# RPI_SmartServo_th_v3.net
KiCad netlist of a schematic drawn in EAGLE
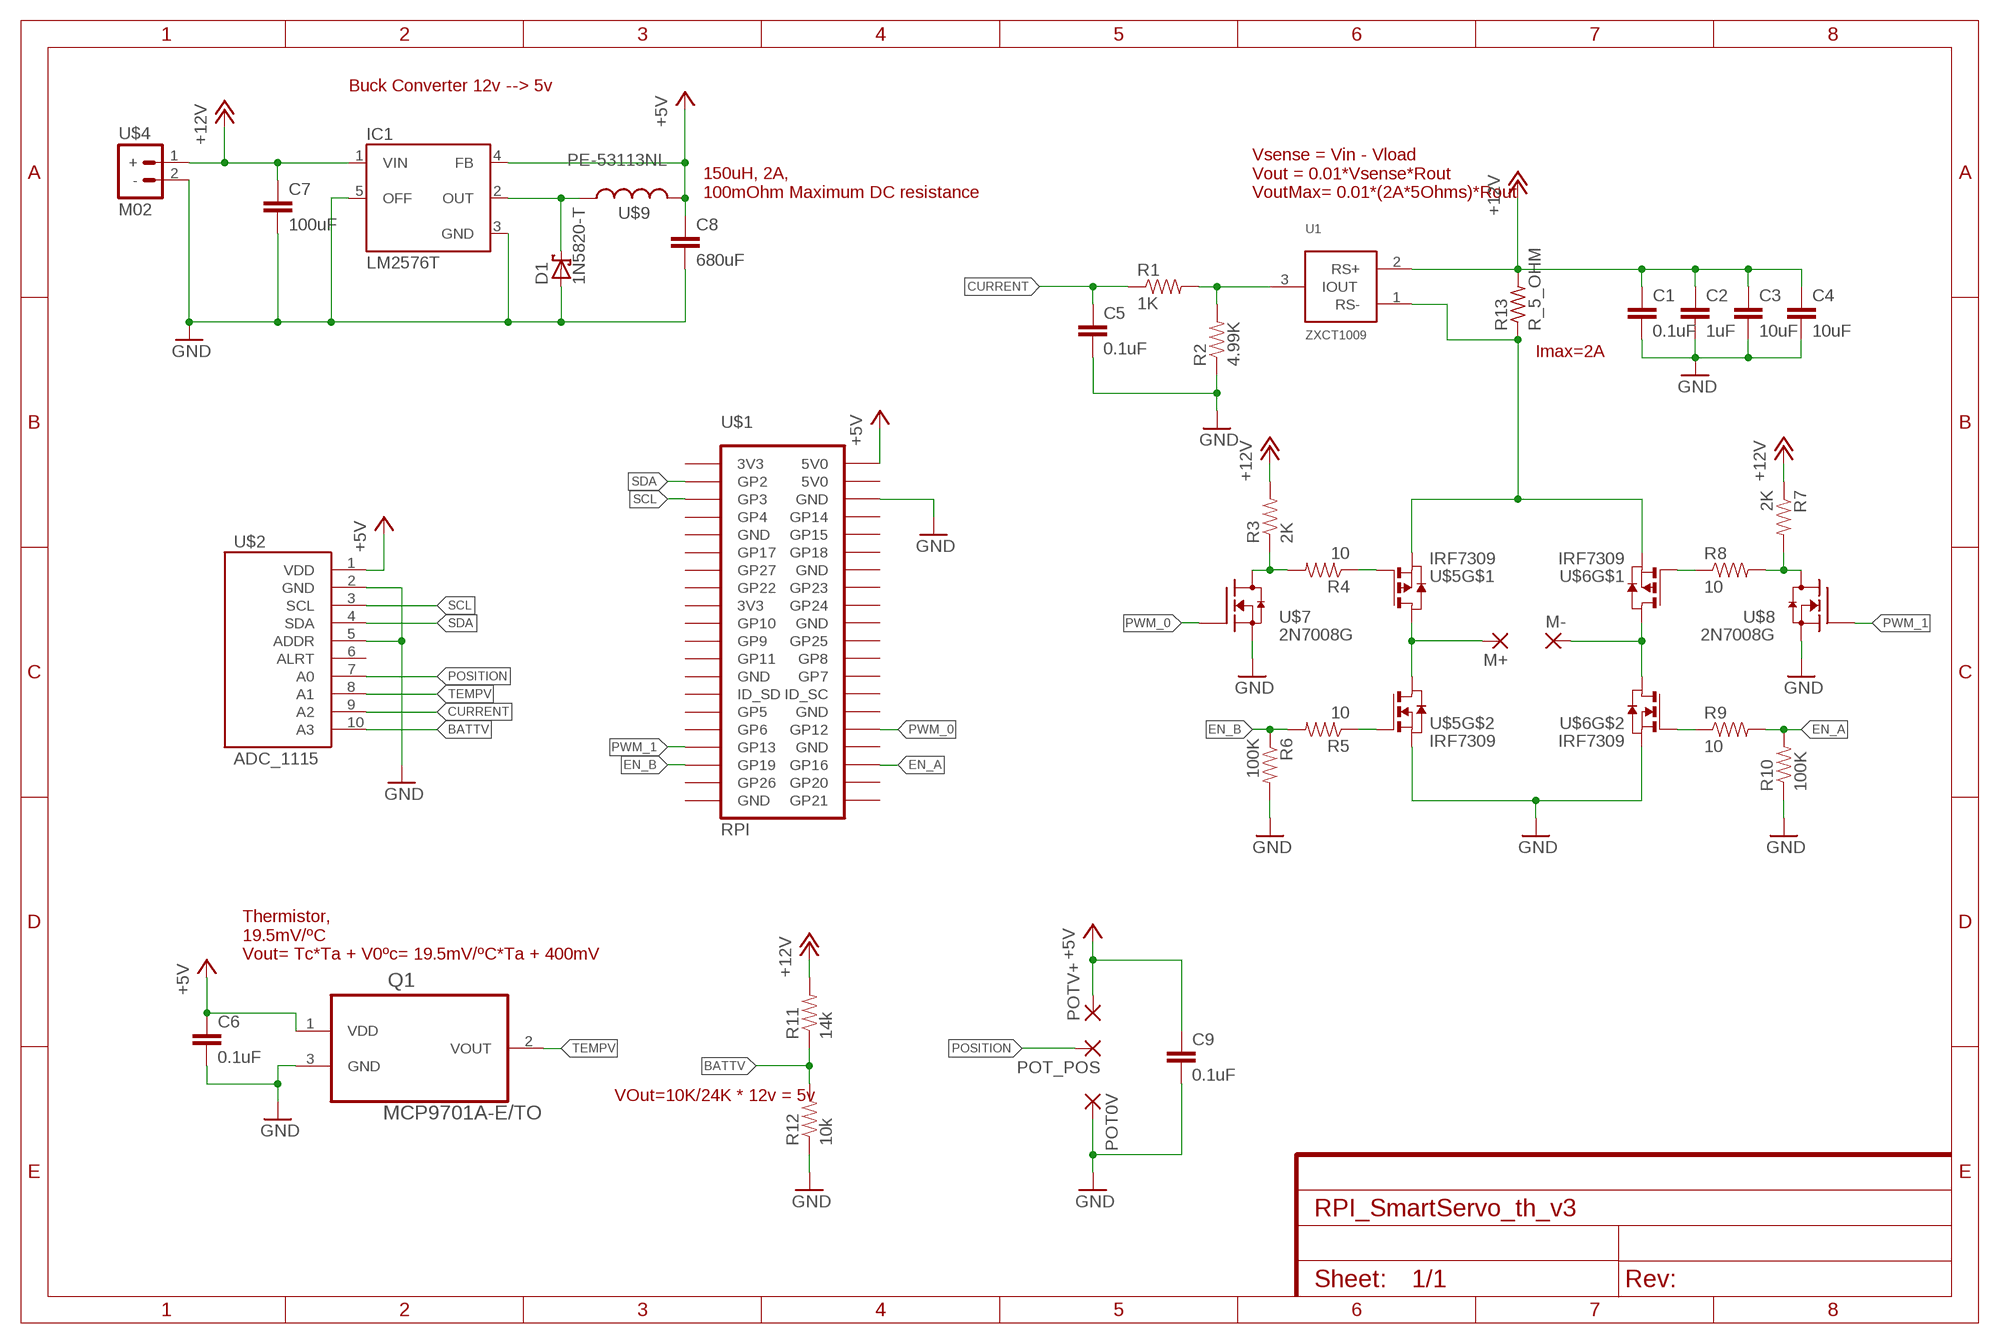
[diagram p0: schematic, sheet 1]

(export (version "E")
  (design (tool "Eeschema 10.0.6"))
  (components
    (comp (ref "C1")
      (value "0.1uF")
      (footprint "eagle-import:C025-025X050")
      (libsource (lib "eagle-import") (part "C-EU025-025X050"))
    )
    (comp (ref "C2")
      (value "1uF")
      (footprint "eagle-import:C025-025X050")
      (libsource (lib "eagle-import") (part "C-EU025-025X050"))
    )
    (comp (ref "C3")
      (value "10uF")
      (footprint "eagle-import:C025-025X050")
      (libsource (lib "eagle-import") (part "C-EU025-025X050"))
    )
    (comp (ref "C4")
      (value "10uF")
      (footprint "eagle-import:C025-025X050")
      (libsource (lib "eagle-import") (part "C-EU025-025X050"))
    )
    (comp (ref "C5")
      (value "0.1uF")
      (footprint "eagle-import:C025-025X050")
      (libsource (lib "eagle-import") (part "C-EU025-025X050"))
    )
    (comp (ref "C6")
      (value "0.1uF")
      (footprint "eagle-import:C025-025X050")
      (libsource (lib "eagle-import") (part "C-EU025-025X050"))
    )
    (comp (ref "C7")
      (value "100uF")
      (footprint "eagle-import:C025-025X050")
      (libsource (lib "eagle-import") (part "C-EU025-025X050"))
    )
    (comp (ref "C8")
      (value "680uF")
      (footprint "eagle-import:C025-025X050")
      (libsource (lib "eagle-import") (part "C-EU025-025X050"))
    )
    (comp (ref "C9")
      (value "0.1uF")
      (footprint "eagle-import:C025-025X050")
      (libsource (lib "eagle-import") (part "C-EU025-025X050"))
    )
    (comp (ref "D1")
      (value "1N5820-T")
      (footprint "eagle-import:C4111-15")
      (libsource (lib "eagle-import") (part "SCHOTTKY-DIODEC4111-15"))
    )
    (comp (ref "IC1")
      (value "LM2576T")
      (footprint "eagle-import:TO220-5")
      (libsource (lib "eagle-import") (part "LM2576T"))
    )
    (comp (ref "M+")
      (value "1,6/0,9")
      (footprint "eagle-import:1,6_0,9")
      (libsource (lib "eagle-import") (part "1,6/0,9"))
    )
    (comp (ref "M-")
      (value "1,6/0,9")
      (footprint "eagle-import:1,6_0,9")
      (libsource (lib "eagle-import") (part "1,6/0,9"))
    )
    (comp (ref "POT0V")
      (value "1,6/0,9")
      (footprint "eagle-import:1,6_0,9")
      (libsource (lib "eagle-import") (part "1,6/0,9"))
    )
    (comp (ref "POTV+")
      (value "1,6/0,9")
      (footprint "eagle-import:1,6_0,9")
      (libsource (lib "eagle-import") (part "1,6/0,9"))
    )
    (comp (ref "POT_POS")
      (value "1,6/0,9")
      (footprint "eagle-import:1,6_0,9")
      (libsource (lib "eagle-import") (part "1,6/0,9"))
    )
    (comp (ref "Q1")
      (value "MCP9701A-E/TO")
      (footprint "eagle-import:TO127P254X533-3")
      (libsource (lib "eagle-import") (part "MCP9701A-E/TO"))
    )
    (comp (ref "R1")
      (value "1K")
      (footprint "eagle-import:AXIAL-0.4")
      (libsource (lib "eagle-import") (part "RESISTORPTH-1/4W"))
    )
    (comp (ref "R2")
      (value "4.99K")
      (footprint "eagle-import:AXIAL-0.4")
      (libsource (lib "eagle-import") (part "RESISTORPTH-1/4W"))
    )
    (comp (ref "R3")
      (value "2K")
      (footprint "eagle-import:AXIAL-0.4")
      (libsource (lib "eagle-import") (part "RESISTORPTH-1/4W"))
    )
    (comp (ref "R4")
      (value "10")
      (footprint "eagle-import:AXIAL-0.4")
      (libsource (lib "eagle-import") (part "RESISTORPTH-1/4W"))
    )
    (comp (ref "R5")
      (value "10")
      (footprint "eagle-import:AXIAL-0.4")
      (libsource (lib "eagle-import") (part "RESISTORPTH-1/4W"))
    )
    (comp (ref "R6")
      (value "100K")
      (footprint "eagle-import:AXIAL-0.4")
      (libsource (lib "eagle-import") (part "RESISTORPTH-1/4W"))
    )
    (comp (ref "R7")
      (value "2K")
      (footprint "eagle-import:AXIAL-0.4")
      (libsource (lib "eagle-import") (part "RESISTORPTH-1/4W"))
    )
    (comp (ref "R8")
      (value "10")
      (footprint "eagle-import:AXIAL-0.4")
      (libsource (lib "eagle-import") (part "RESISTORPTH-1/4W"))
    )
    (comp (ref "R9")
      (value "10")
      (footprint "eagle-import:AXIAL-0.4")
      (libsource (lib "eagle-import") (part "RESISTORPTH-1/4W"))
    )
    (comp (ref "R10")
      (value "100K")
      (footprint "eagle-import:AXIAL-0.4")
      (libsource (lib "eagle-import") (part "RESISTORPTH-1/4W"))
    )
    (comp (ref "R11")
      (value "14k")
      (footprint "eagle-import:AXIAL-0.4")
      (libsource (lib "eagle-import") (part "RESISTORPTH-1/4W"))
    )
    (comp (ref "R12")
      (value "10k")
      (footprint "eagle-import:AXIAL-0.4")
      (libsource (lib "eagle-import") (part "RESISTORPTH-1/4W"))
    )
    (comp (ref "R13")
      (value "R_5_OHM")
      (footprint "eagle-import:0922_22")
      (libsource (lib "eagle-import") (part "R_5_OHM"))
    )
    (comp (ref "U$1")
      (value "RPI")
      (footprint "eagle-import:2X20")
      (libsource (lib "eagle-import") (part "RPI"))
    )
    (comp (ref "U$2")
      (value "ADC_1115")
      (footprint "eagle-import:1X10")
      (libsource (lib "eagle-import") (part "ADC_1115"))
    )
    (comp (ref "U$4")
      (value "M02")
      (footprint "eagle-import:1X02")
      (libsource (lib "eagle-import") (part "M02"))
    )
    (comp (ref "U$5")
      (value "IRF7309")
      (footprint "eagle-import:SO8")
      (libsource (lib "eagle-import") (part "IRF7309"))
    )
    (comp (ref "U$6")
      (value "IRF7309")
      (footprint "eagle-import:SO8")
      (libsource (lib "eagle-import") (part "IRF7309"))
    )
    (comp (ref "U$7")
      (value "2N7008G")
      (footprint "eagle-import:TO-92")
      (libsource (lib "eagle-import") (part "2N7008G"))
    )
    (comp (ref "U$8")
      (value "2N7008G")
      (footprint "eagle-import:TO-92")
      (libsource (lib "eagle-import") (part "2N7008G"))
    )
    (comp (ref "U$9")
      (value "PE-53113NL")
      (footprint "eagle-import:KM-4")
      (libsource (lib "eagle-import") (part "PE-53113NL"))
    )
    (comp (ref "U1")
      (value "ZXCT1009")
      (footprint "eagle-import:SOT23")
      (libsource (lib "eagle-import") (part "ZXCT1009"))
    )
  )
  (nets
    (net (code "1") (name "+5V") (class "Default")
      (node (ref "C6") (pin "1") (pinfunction "1_1") (pintype "passive"))
      (node (ref "C8") (pin "1") (pinfunction "1_1") (pintype "passive"))
      (node (ref "C9") (pin "1") (pinfunction "1_1") (pintype "passive"))
      (node (ref "IC1") (pin "4") (pinfunction "FB_4") (pintype "input"))
      (node (ref "POTV+") (pin "1") (pinfunction "P_1") (pintype "passive"))
      (node (ref "Q1") (pin "1") (pinfunction "VDD_1") (pintype "power_in"))
      (node (ref "U$1") (pin "2") (pinfunction "5V0_2") (pintype "bidirectional"))
      (node (ref "U$2") (pin "1") (pinfunction "VDD_1") (pintype "bidirectional"))
      (node (ref "U$9") (pin "P$2") (pinfunction "2_P$2") (pintype "passive"))
    )
    (net (code "2") (name "+12V") (class "Default")
      (node (ref "C1") (pin "1") (pinfunction "1_1") (pintype "passive"))
      (node (ref "C2") (pin "1") (pinfunction "1_1") (pintype "passive"))
      (node (ref "C3") (pin "1") (pinfunction "1_1") (pintype "passive"))
      (node (ref "C4") (pin "1") (pinfunction "1_1") (pintype "passive"))
      (node (ref "C7") (pin "1") (pinfunction "1_1") (pintype "passive"))
      (node (ref "IC1") (pin "1") (pinfunction "VIN_1") (pintype "power_in"))
      (node (ref "R11") (pin "P$2") (pinfunction "2_P$2") (pintype "passive"))
      (node (ref "R13") (pin "2") (pinfunction "2_2") (pintype "passive"))
      (node (ref "R3") (pin "P$2") (pinfunction "2_P$2") (pintype "passive"))
      (node (ref "R7") (pin "P$1") (pinfunction "1_P$1") (pintype "passive"))
      (node (ref "U$4") (pin "1") (pinfunction "+_1") (pintype "passive"))
      (node (ref "U1") (pin "2") (pinfunction "RS+_2") (pintype "bidirectional"))
    )
    (net (code "3") (name "BATTV") (class "Default")
      (node (ref "R11") (pin "P$1") (pinfunction "1_P$1") (pintype "passive"))
      (node (ref "R12") (pin "P$2") (pinfunction "2_P$2") (pintype "passive"))
      (node (ref "U$2") (pin "10") (pinfunction "A3_10") (pintype "bidirectional"))
    )
    (net (code "4") (name "CURRENT") (class "Default")
      (node (ref "C5") (pin "1") (pinfunction "1_1") (pintype "passive"))
      (node (ref "R1") (pin "P$1") (pinfunction "1_P$1") (pintype "passive"))
      (node (ref "U$2") (pin "9") (pinfunction "A2_9") (pintype "bidirectional"))
    )
    (net (code "5") (name "EN_A") (class "Default")
      (node (ref "R10") (pin "P$2") (pinfunction "2_P$2") (pintype "passive"))
      (node (ref "R9") (pin "P$2") (pinfunction "2_P$2") (pintype "passive"))
      (node (ref "U$1") (pin "36") (pinfunction "GP16_36") (pintype "bidirectional"))
    )
    (net (code "6") (name "EN_B") (class "Default")
      (node (ref "R5") (pin "P$2") (pinfunction "2_P$2") (pintype "passive"))
      (node (ref "R6") (pin "P$1") (pinfunction "1_P$1") (pintype "passive"))
      (node (ref "U$1") (pin "35") (pinfunction "GP19_35") (pintype "bidirectional"))
    )
    (net (code "7") (name "GND") (class "Default")
      (node (ref "C1") (pin "2") (pinfunction "2_2") (pintype "passive"))
      (node (ref "C2") (pin "2") (pinfunction "2_2") (pintype "passive"))
      (node (ref "C3") (pin "2") (pinfunction "2_2") (pintype "passive"))
      (node (ref "C4") (pin "2") (pinfunction "2_2") (pintype "passive"))
      (node (ref "C5") (pin "2") (pinfunction "2_2") (pintype "passive"))
      (node (ref "C6") (pin "2") (pinfunction "2_2") (pintype "passive"))
      (node (ref "C7") (pin "2") (pinfunction "2_2") (pintype "passive"))
      (node (ref "C8") (pin "2") (pinfunction "2_2") (pintype "passive"))
      (node (ref "C9") (pin "2") (pinfunction "2_2") (pintype "passive"))
      (node (ref "D1") (pin "A") (pinfunction "A_A") (pintype "passive"))
      (node (ref "IC1") (pin "3") (pinfunction "GND_3") (pintype "power_in"))
      (node (ref "IC1") (pin "5") (pinfunction "OFF_5") (pintype "input"))
      (node (ref "POT0V") (pin "1") (pinfunction "P_1") (pintype "passive"))
      (node (ref "Q1") (pin "3") (pinfunction "GND_3") (pintype "passive"))
      (node (ref "R10") (pin "P$1") (pinfunction "1_P$1") (pintype "passive"))
      (node (ref "R12") (pin "P$1") (pinfunction "1_P$1") (pintype "passive"))
      (node (ref "R2") (pin "P$1") (pinfunction "1_P$1") (pintype "passive"))
      (node (ref "R6") (pin "P$2") (pinfunction "2_P$2") (pintype "passive"))
      (node (ref "U$1") (pin "6") (pinfunction "GND_6") (pintype "bidirectional"))
      (node (ref "U$2") (pin "2") (pinfunction "GND_2") (pintype "bidirectional"))
      (node (ref "U$2") (pin "5") (pinfunction "ADDR_5") (pintype "bidirectional"))
      (node (ref "U$4") (pin "2") (pinfunction "-_2") (pintype "passive"))
      (node (ref "U$5") (pin "1") (pinfunction "S_1") (pintype "passive"))
      (node (ref "U$6") (pin "1") (pinfunction "S_1") (pintype "passive"))
      (node (ref "U$7") (pin "1") (pinfunction "S_1") (pintype "passive"))
      (node (ref "U$8") (pin "1") (pinfunction "S_1") (pintype "passive"))
    )
    (net (code "8") (name "Net-(IC1-OUT)") (class "Default")
      (node (ref "D1") (pin "C") (pinfunction "C_C") (pintype "passive"))
      (node (ref "IC1") (pin "2") (pinfunction "OUT_2") (pintype "output"))
      (node (ref "U$9") (pin "P$1") (pinfunction "1_P$1") (pintype "passive"))
    )
    (net (code "9") (name "Net-(M+-P)") (class "Default")
      (node (ref "M+") (pin "1") (pinfunction "P_1") (pintype "passive"))
      (node (ref "U$5") (pin "5") (pinfunction "D_5") (pintype "passive"))
      (node (ref "U$5") (pin "6") (pinfunction "D_6") (pintype "passive"))
      (node (ref "U$5") (pin "7") (pinfunction "D_7") (pintype "passive"))
      (node (ref "U$5") (pin "8") (pinfunction "D_8") (pintype "passive"))
    )
    (net (code "10") (name "Net-(M--P)") (class "Default")
      (node (ref "M-") (pin "1") (pinfunction "P_1") (pintype "passive"))
      (node (ref "U$6") (pin "5") (pinfunction "D_5") (pintype "passive"))
      (node (ref "U$6") (pin "6") (pinfunction "D_6") (pintype "passive"))
      (node (ref "U$6") (pin "7") (pinfunction "D_7") (pintype "passive"))
      (node (ref "U$6") (pin "8") (pinfunction "D_8") (pintype "passive"))
    )
    (net (code "11") (name "Net-(R1-2)") (class "Default")
      (node (ref "R1") (pin "P$2") (pinfunction "2_P$2") (pintype "passive"))
      (node (ref "R2") (pin "P$2") (pinfunction "2_P$2") (pintype "passive"))
      (node (ref "U1") (pin "3") (pinfunction "IOUT_3") (pintype "bidirectional"))
    )
    (net (code "12") (name "Net-(R3-1)") (class "Default")
      (node (ref "R3") (pin "P$1") (pinfunction "1_P$1") (pintype "passive"))
      (node (ref "R4") (pin "P$2") (pinfunction "2_P$2") (pintype "passive"))
      (node (ref "U$7") (pin "3") (pinfunction "D_3") (pintype "passive"))
    )
    (net (code "13") (name "Net-(R4-1)") (class "Default")
      (node (ref "R4") (pin "P$1") (pinfunction "1_P$1") (pintype "passive"))
      (node (ref "U$5") (pin "4") (pinfunction "G_4") (pintype "passive"))
    )
    (net (code "14") (name "Net-(R5-1)") (class "Default")
      (node (ref "R5") (pin "P$1") (pinfunction "1_P$1") (pintype "passive"))
      (node (ref "U$5") (pin "2") (pinfunction "G_2") (pintype "passive"))
    )
    (net (code "15") (name "Net-(R7-2)") (class "Default")
      (node (ref "R7") (pin "P$2") (pinfunction "2_P$2") (pintype "passive"))
      (node (ref "R8") (pin "P$2") (pinfunction "2_P$2") (pintype "passive"))
      (node (ref "U$8") (pin "3") (pinfunction "D_3") (pintype "passive"))
    )
    (net (code "16") (name "Net-(R8-1)") (class "Default")
      (node (ref "R8") (pin "P$1") (pinfunction "1_P$1") (pintype "passive"))
      (node (ref "U$6") (pin "4") (pinfunction "G_4") (pintype "passive"))
    )
    (net (code "17") (name "Net-(R9-1)") (class "Default")
      (node (ref "R9") (pin "P$1") (pinfunction "1_P$1") (pintype "passive"))
      (node (ref "U$6") (pin "2") (pinfunction "G_2") (pintype "passive"))
    )
    (net (code "18") (name "Net-(U$5A-S)") (class "Default")
      (node (ref "R13") (pin "1") (pinfunction "1_1") (pintype "passive"))
      (node (ref "U$5") (pin "3") (pinfunction "S_3") (pintype "passive"))
      (node (ref "U$6") (pin "3") (pinfunction "S_3") (pintype "passive"))
      (node (ref "U1") (pin "1") (pinfunction "RS-_1") (pintype "bidirectional"))
    )
    (net (code "19") (name "POSITION") (class "Default")
      (node (ref "POT_POS") (pin "1") (pinfunction "P_1") (pintype "passive"))
      (node (ref "U$2") (pin "7") (pinfunction "A0_7") (pintype "bidirectional"))
    )
    (net (code "20") (name "PWM_0") (class "Default")
      (node (ref "U$1") (pin "32") (pinfunction "GP12_32") (pintype "bidirectional"))
      (node (ref "U$7") (pin "2") (pinfunction "G_2") (pintype "passive"))
    )
    (net (code "21") (name "PWM_1") (class "Default")
      (node (ref "U$1") (pin "33") (pinfunction "GP13_33") (pintype "bidirectional"))
      (node (ref "U$8") (pin "2") (pinfunction "G_2") (pintype "passive"))
    )
    (net (code "22") (name "SCL") (class "Default")
      (node (ref "U$1") (pin "5") (pinfunction "GP3_5") (pintype "bidirectional"))
      (node (ref "U$2") (pin "3") (pinfunction "SCL_3") (pintype "bidirectional"))
    )
    (net (code "23") (name "SDA") (class "Default")
      (node (ref "U$1") (pin "3") (pinfunction "GP2_3") (pintype "bidirectional"))
      (node (ref "U$2") (pin "4") (pinfunction "SDA_4") (pintype "bidirectional"))
    )
    (net (code "24") (name "TEMPV") (class "Default")
      (node (ref "Q1") (pin "2") (pinfunction "VOUT_2") (pintype "output"))
      (node (ref "U$2") (pin "8") (pinfunction "A1_8") (pintype "bidirectional"))
    )
    (net (code "25") (name "unconnected-(U$1-3V3-Pad1)") (class "Default")
      (node (ref "U$1") (pin "1") (pinfunction "3V3_1") (pintype "bidirectional"))
    )
    (net (code "26") (name "unconnected-(U$1-3V3-Pad17)") (class "Default")
      (node (ref "U$1") (pin "17") (pinfunction "3V3_17") (pintype "bidirectional"))
    )
    (net (code "27") (name "unconnected-(U$1-5V0-Pad4)") (class "Default")
      (node (ref "U$1") (pin "4") (pinfunction "5V0_4") (pintype "bidirectional"))
    )
    (net (code "28") (name "unconnected-(U$1-GND-Pad9)") (class "Default")
      (node (ref "U$1") (pin "9") (pinfunction "GND_9") (pintype "bidirectional"))
    )
    (net (code "29") (name "unconnected-(U$1-GND-Pad14)") (class "Default")
      (node (ref "U$1") (pin "14") (pinfunction "GND_14") (pintype "bidirectional"))
    )
    (net (code "30") (name "unconnected-(U$1-GND-Pad20)") (class "Default")
      (node (ref "U$1") (pin "20") (pinfunction "GND_20") (pintype "bidirectional"))
    )
    (net (code "31") (name "unconnected-(U$1-GND-Pad25)") (class "Default")
      (node (ref "U$1") (pin "25") (pinfunction "GND_25") (pintype "bidirectional"))
    )
    (net (code "32") (name "unconnected-(U$1-GND-Pad30)") (class "Default")
      (node (ref "U$1") (pin "30") (pinfunction "GND_30") (pintype "bidirectional"))
    )
    (net (code "33") (name "unconnected-(U$1-GND-Pad34)") (class "Default")
      (node (ref "U$1") (pin "34") (pinfunction "GND_34") (pintype "bidirectional"))
    )
    (net (code "34") (name "unconnected-(U$1-GND-Pad39)") (class "Default")
      (node (ref "U$1") (pin "39") (pinfunction "GND_39") (pintype "bidirectional"))
    )
    (net (code "35") (name "unconnected-(U$1-GP4-Pad7)") (class "Default")
      (node (ref "U$1") (pin "7") (pinfunction "GP4_7") (pintype "bidirectional"))
    )
    (net (code "36") (name "unconnected-(U$1-GP5-Pad29)") (class "Default")
      (node (ref "U$1") (pin "29") (pinfunction "GP5_29") (pintype "bidirectional"))
    )
    (net (code "37") (name "unconnected-(U$1-GP6-Pad31)") (class "Default")
      (node (ref "U$1") (pin "31") (pinfunction "GP6_31") (pintype "bidirectional"))
    )
    (net (code "38") (name "unconnected-(U$1-GP7-Pad26)") (class "Default")
      (node (ref "U$1") (pin "26") (pinfunction "GP7_26") (pintype "bidirectional"))
    )
    (net (code "39") (name "unconnected-(U$1-GP8-Pad24)") (class "Default")
      (node (ref "U$1") (pin "24") (pinfunction "GP8_24") (pintype "bidirectional"))
    )
    (net (code "40") (name "unconnected-(U$1-GP9-Pad21)") (class "Default")
      (node (ref "U$1") (pin "21") (pinfunction "GP9_21") (pintype "bidirectional"))
    )
    (net (code "41") (name "unconnected-(U$1-GP10-Pad19)") (class "Default")
      (node (ref "U$1") (pin "19") (pinfunction "GP10_19") (pintype "bidirectional"))
    )
    (net (code "42") (name "unconnected-(U$1-GP11-Pad23)") (class "Default")
      (node (ref "U$1") (pin "23") (pinfunction "GP11_23") (pintype "bidirectional"))
    )
    (net (code "43") (name "unconnected-(U$1-GP14-Pad8)") (class "Default")
      (node (ref "U$1") (pin "8") (pinfunction "GP14_8") (pintype "bidirectional"))
    )
    (net (code "44") (name "unconnected-(U$1-GP15-Pad10)") (class "Default")
      (node (ref "U$1") (pin "10") (pinfunction "GP15_10") (pintype "bidirectional"))
    )
    (net (code "45") (name "unconnected-(U$1-GP17-Pad11)") (class "Default")
      (node (ref "U$1") (pin "11") (pinfunction "GP17_11") (pintype "bidirectional"))
    )
    (net (code "46") (name "unconnected-(U$1-GP18-Pad12)") (class "Default")
      (node (ref "U$1") (pin "12") (pinfunction "GP18_12") (pintype "bidirectional"))
    )
    (net (code "47") (name "unconnected-(U$1-GP20-Pad38)") (class "Default")
      (node (ref "U$1") (pin "38") (pinfunction "GP20_38") (pintype "bidirectional"))
    )
    (net (code "48") (name "unconnected-(U$1-GP21-Pad40)") (class "Default")
      (node (ref "U$1") (pin "40") (pinfunction "GP21_40") (pintype "bidirectional"))
    )
    (net (code "49") (name "unconnected-(U$1-GP22-Pad15)") (class "Default")
      (node (ref "U$1") (pin "15") (pinfunction "GP22_15") (pintype "bidirectional"))
    )
    (net (code "50") (name "unconnected-(U$1-GP23-Pad16)") (class "Default")
      (node (ref "U$1") (pin "16") (pinfunction "GP23_16") (pintype "bidirectional"))
    )
    (net (code "51") (name "unconnected-(U$1-GP24-Pad18)") (class "Default")
      (node (ref "U$1") (pin "18") (pinfunction "GP24_18") (pintype "bidirectional"))
    )
    (net (code "52") (name "unconnected-(U$1-GP25-Pad22)") (class "Default")
      (node (ref "U$1") (pin "22") (pinfunction "GP25_22") (pintype "bidirectional"))
    )
    (net (code "53") (name "unconnected-(U$1-GP26-Pad37)") (class "Default")
      (node (ref "U$1") (pin "37") (pinfunction "GP26_37") (pintype "bidirectional"))
    )
    (net (code "54") (name "unconnected-(U$1-GP27-Pad13)") (class "Default")
      (node (ref "U$1") (pin "13") (pinfunction "GP27_13") (pintype "bidirectional"))
    )
    (net (code "55") (name "unconnected-(U$1-ID_SC-Pad28)") (class "Default")
      (node (ref "U$1") (pin "28") (pinfunction "ID_SC_28") (pintype "bidirectional"))
    )
    (net (code "56") (name "unconnected-(U$1-ID_SD-Pad27)") (class "Default")
      (node (ref "U$1") (pin "27") (pinfunction "ID_SD_27") (pintype "bidirectional"))
    )
    (net (code "57") (name "unconnected-(U$2-ALRT-Pad6)") (class "Default")
      (node (ref "U$2") (pin "6") (pinfunction "ALRT_6") (pintype "bidirectional"))
    )
  )
)
